# UV16_PDU.net
KiCad netlist of a schematic drawn in Altium Designer
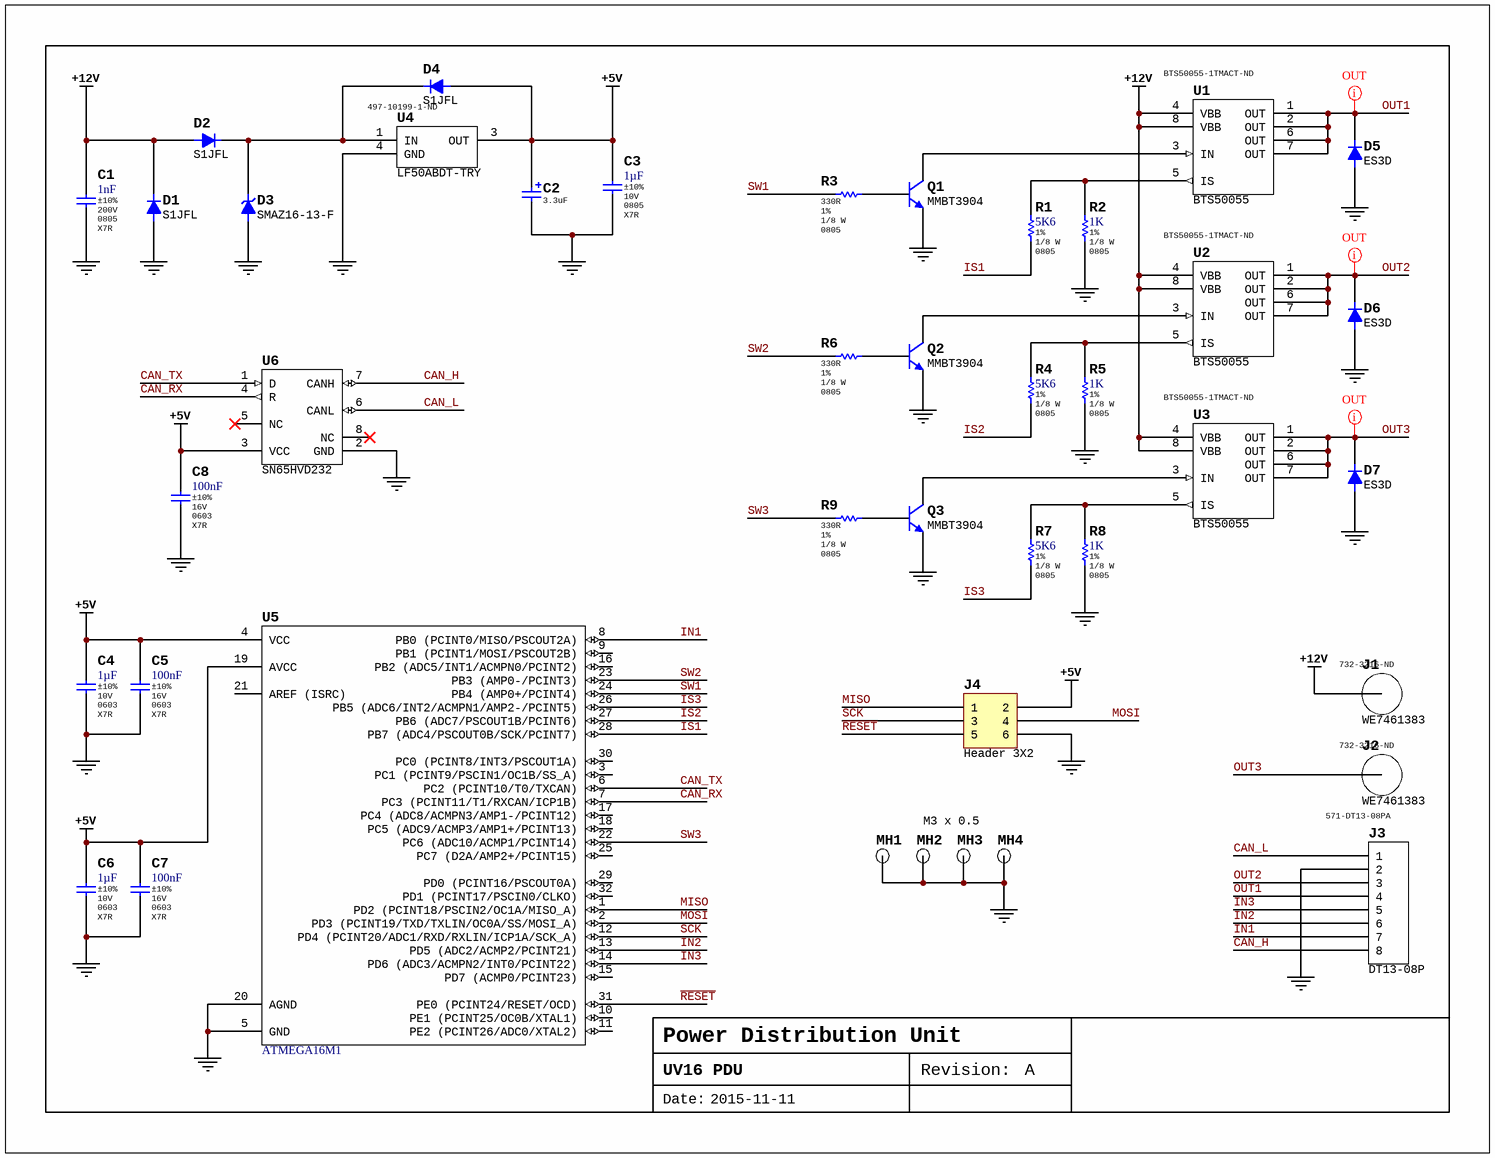
[diagram p0: UV16 PDU.SchDoc]

(export (version "E")
  (design (tool "Eeschema 10.0.6"))
  (components
    (comp (ref "C1")
      (value "1nF")
      (footprint "CAP-0805-M")
      (fields
        (field (name "PART NUMBER") "CC0805KRX7RABB102")
        (field (name "TOLERANCE") "±10%")
        (field (name "VOLTAGE") "200V")
        (field (name "PACKAGE") "0805")
        (field (name "TEMPERATURE COEFFICIENT") "X7R")
        (field (name "MANUFACTURER") "Yageo")
      )
      (libsource (lib "Capacitors") (part "Capacitor"))
    )
    (comp (ref "C2")
      (value "3.3uF")
      (footprint "CAPMP6032X21M")
      (fields (field (name "Comment") "TPSC335K035R0700"))
      (libsource (lib "UV16 PDU") (part "TPSC335K035R0700"))
    )
    (comp (ref "C3")
      (value "1µF")
      (footprint "CAP-0805-M")
      (fields
        (field (name "PART NUMBER") "CC0805KKX7R6BB105")
        (field (name "TOLERANCE") "±10%")
        (field (name "VOLTAGE") "10V")
        (field (name "PACKAGE") "0805")
        (field (name "TEMPERATURE COEFFICIENT") "X7R")
        (field (name "MANUFACTURER") "Yageo")
      )
      (libsource (lib "Capacitors") (part "Capacitor"))
    )
    (comp (ref "C4")
      (value "1µF")
      (footprint "CAP-0603-M")
      (fields
        (field (name "PART NUMBER") "CC0603KRX7R6BB105")
        (field (name "TOLERANCE") "±10%")
        (field (name "VOLTAGE") "10V")
        (field (name "PACKAGE") "0603")
        (field (name "TEMPERATURE COEFFICIENT") "X7R")
        (field (name "MANUFACTURER") "Yageo")
      )
      (libsource (lib "Capacitors") (part "Capacitor"))
    )
    (comp (ref "C5")
      (value "100nF")
      (footprint "CAP-0603-M")
      (fields
        (field (name "PART NUMBER") "CC0603KPX7R7BB104")
        (field (name "TOLERANCE") "±10%")
        (field (name "VOLTAGE") "16V")
        (field (name "PACKAGE") "0603")
        (field (name "TEMPERATURE COEFFICIENT") "X7R")
        (field (name "MANUFACTURER") "Yageo")
      )
      (libsource (lib "Capacitors") (part "Capacitor"))
    )
    (comp (ref "C6")
      (value "1µF")
      (footprint "CAP-0603-M")
      (fields
        (field (name "PART NUMBER") "CC0603KRX7R6BB105")
        (field (name "TOLERANCE") "±10%")
        (field (name "VOLTAGE") "10V")
        (field (name "PACKAGE") "0603")
        (field (name "TEMPERATURE COEFFICIENT") "X7R")
        (field (name "MANUFACTURER") "Yageo")
      )
      (libsource (lib "Capacitors") (part "Capacitor"))
    )
    (comp (ref "C7")
      (value "100nF")
      (footprint "CAP-0603-M")
      (fields
        (field (name "PART NUMBER") "CC0603KPX7R7BB104")
        (field (name "TOLERANCE") "±10%")
        (field (name "VOLTAGE") "16V")
        (field (name "PACKAGE") "0603")
        (field (name "TEMPERATURE COEFFICIENT") "X7R")
        (field (name "MANUFACTURER") "Yageo")
      )
      (libsource (lib "Capacitors") (part "Capacitor"))
    )
    (comp (ref "C8")
      (value "100nF")
      (footprint "CAP-0603-M")
      (fields
        (field (name "PART NUMBER") "CC0603KPX7R7BB104")
        (field (name "TOLERANCE") "±10%")
        (field (name "VOLTAGE") "16V")
        (field (name "PACKAGE") "0603")
        (field (name "TEMPERATURE COEFFICIENT") "X7R")
        (field (name "MANUFACTURER") "Yageo")
      )
      (libsource (lib "Capacitors") (part "Capacitor"))
    )
    (comp (ref "D1") (value "S1JFL") (footprint "DIOM3617X11M") (libsource (lib "UV16 PDU") (part "S1JFL")))
    (comp (ref "D2") (value "S1JFL") (footprint "DIOM3617X11M") (libsource (lib "UV16 PDU") (part "S1JFL")))
    (comp (ref "D3")
      (value "SMAZ16-13-F")
      (footprint "DIOM4326X23M")
      (libsource (lib "UV16 PDU") (part "SMAZ16-13-F"))
    )
    (comp (ref "D4") (value "S1JFL") (footprint "DIOM3617X11M") (libsource (lib "UV16 PDU") (part "S1JFL")))
    (comp (ref "D5") (value "ES3D") (footprint "DIOM6959X26M") (libsource (lib "UV16 PDU") (part "ES3D")))
    (comp (ref "D6") (value "ES3D") (footprint "DIOM6959X26M") (libsource (lib "UV16 PDU") (part "ES3D")))
    (comp (ref "D7") (value "ES3D") (footprint "DIOM6959X26M") (libsource (lib "UV16 PDU") (part "ES3D")))
    (comp (ref "J1")
      (value "WE7461383")
      (footprint "WE7461383")
      (fields (field (name "SUPPLIER PART NUMBER 1") "732-3216-ND"))
      (libsource (lib "UV16 PDU") (part "WE7461383"))
    )
    (comp (ref "J2")
      (value "WE7461383")
      (footprint "WE7461383")
      (fields (field (name "SUPPLIER PART NUMBER 1") "732-3216-ND"))
      (libsource (lib "UV16 PDU") (part "WE7461383"))
    )
    (comp (ref "J3")
      (value "DT13-08P")
      (footprint "DT13-08P")
      (description "DT Series 8-Pin Right Angle PCB Mount Receptacle")
      (fields (field (name "SUPPLIER PART NUMBER 1") "571-DT13-08PA"))
      (libsource (lib "UV16 PDU") (part "DT13-08P"))
    )
    (comp (ref "J4")
      (value "Header 3X2")
      (footprint "HDR2X3")
      (description "Header, 3-Pin, Dual row")
      (fields (field (name "PUBLISHER") "Altium Limited"))
      (libsource (lib "Miscellaneous Connectors") (part "Header 3X2"))
    )
    (comp (ref "MH1")
      (value "M3 x 0.5")
      (footprint "MH-M3-0.5")
      (libsource (lib "UV16 PDU") (part "MH-M3-0.5"))
    )
    (comp (ref "MH2")
      (value "M3 x 0.5")
      (footprint "MH-M3-0.5")
      (libsource (lib "UV16 PDU") (part "MH-M3-0.5"))
    )
    (comp (ref "MH3")
      (value "M3 x 0.5")
      (footprint "MH-M3-0.5")
      (libsource (lib "UV16 PDU") (part "MH-M3-0.5"))
    )
    (comp (ref "MH4")
      (value "M3 x 0.5")
      (footprint "MH-M3-0.5")
      (libsource (lib "UV16 PDU") (part "MH-M3-0.5"))
    )
    (comp (ref "Q1") (value "MMBT3904") (footprint "SOT23-3") (libsource (lib "UV16 PDU") (part "MMBT3904")))
    (comp (ref "Q2") (value "MMBT3904") (footprint "SOT23-3") (libsource (lib "UV16 PDU") (part "MMBT3904")))
    (comp (ref "Q3") (value "MMBT3904") (footprint "SOT23-3") (libsource (lib "UV16 PDU") (part "MMBT3904")))
    (comp (ref "R1")
      (value "5K6")
      (footprint "RES-0805-M")
      (fields
        (field (name "PART NUMBER") "RC0805FR-075K6L")
        (field (name "TOLERANCE") "1%")
        (field (name "POWER") "1/8 W")
        (field (name "PACKAGE") "0805")
        (field (name "MANUFACTURER") "Yageo")
      )
      (libsource (lib "Resistors") (part "Resistor"))
    )
    (comp (ref "R2")
      (value "1K")
      (footprint "RES-0805-M")
      (fields
        (field (name "PART NUMBER") "RC0805FR-071KL")
        (field (name "TOLERANCE") "1%")
        (field (name "POWER") "1/8 W")
        (field (name "PACKAGE") "0805")
        (field (name "MANUFACTURER") "Yageo")
      )
      (libsource (lib "Resistors") (part "Resistor"))
    )
    (comp (ref "R3")
      (value "330R")
      (footprint "RES-0805-M")
      (fields
        (field (name "PART NUMBER") "RC0805FR-07330RL")
        (field (name "TOLERANCE") "1%")
        (field (name "POWER") "1/8 W")
        (field (name "PACKAGE") "0805")
        (field (name "MANUFACTURER") "Yageo")
      )
      (libsource (lib "Resistors") (part "Resistor"))
    )
    (comp (ref "R4")
      (value "5K6")
      (footprint "RES-0805-M")
      (fields
        (field (name "PART NUMBER") "RC0805FR-075K6L")
        (field (name "TOLERANCE") "1%")
        (field (name "POWER") "1/8 W")
        (field (name "PACKAGE") "0805")
        (field (name "MANUFACTURER") "Yageo")
      )
      (libsource (lib "Resistors") (part "Resistor"))
    )
    (comp (ref "R5")
      (value "1K")
      (footprint "RES-0805-M")
      (fields
        (field (name "PART NUMBER") "RC0805FR-071KL")
        (field (name "TOLERANCE") "1%")
        (field (name "POWER") "1/8 W")
        (field (name "PACKAGE") "0805")
        (field (name "MANUFACTURER") "Yageo")
      )
      (libsource (lib "Resistors") (part "Resistor"))
    )
    (comp (ref "R6")
      (value "330R")
      (footprint "RES-0805-M")
      (fields
        (field (name "PART NUMBER") "RC0805FR-07330RL")
        (field (name "TOLERANCE") "1%")
        (field (name "POWER") "1/8 W")
        (field (name "PACKAGE") "0805")
        (field (name "MANUFACTURER") "Yageo")
      )
      (libsource (lib "Resistors") (part "Resistor"))
    )
    (comp (ref "R7")
      (value "5K6")
      (footprint "RES-0805-M")
      (fields
        (field (name "PART NUMBER") "RC0805FR-075K6L")
        (field (name "TOLERANCE") "1%")
        (field (name "POWER") "1/8 W")
        (field (name "PACKAGE") "0805")
        (field (name "MANUFACTURER") "Yageo")
      )
      (libsource (lib "Resistors") (part "Resistor"))
    )
    (comp (ref "R8")
      (value "1K")
      (footprint "RES-0805-M")
      (fields
        (field (name "PART NUMBER") "RC0805FR-071KL")
        (field (name "TOLERANCE") "1%")
        (field (name "POWER") "1/8 W")
        (field (name "PACKAGE") "0805")
        (field (name "MANUFACTURER") "Yageo")
      )
      (libsource (lib "Resistors") (part "Resistor"))
    )
    (comp (ref "R9")
      (value "330R")
      (footprint "RES-0805-M")
      (fields
        (field (name "PART NUMBER") "RC0805FR-07330RL")
        (field (name "TOLERANCE") "1%")
        (field (name "POWER") "1/8 W")
        (field (name "PACKAGE") "0805")
        (field (name "MANUFACTURER") "Yageo")
      )
      (libsource (lib "Resistors") (part "Resistor"))
    )
    (comp (ref "U1")
      (value "BTS50055")
      (footprint "P/PG-TO220-7-4")
      (fields (field (name "SUPPLIER PART NUMBER 1") "BTS50055-1TMACT-ND"))
      (libsource (lib "UV16 PDU") (part "BTS50055"))
    )
    (comp (ref "U2")
      (value "BTS50055")
      (footprint "P/PG-TO220-7-4")
      (fields (field (name "SUPPLIER PART NUMBER 1") "BTS50055-1TMACT-ND"))
      (libsource (lib "UV16 PDU") (part "BTS50055"))
    )
    (comp (ref "U3")
      (value "BTS50055")
      (footprint "P/PG-TO220-7-4")
      (fields (field (name "SUPPLIER PART NUMBER 1") "BTS50055-1TMACT-ND"))
      (libsource (lib "UV16 PDU") (part "BTS50055"))
    )
    (comp (ref "U4")
      (value "LF50ABDT-TRY")
      (footprint "TO-252-3")
      (fields (field (name "SUPPLIER PART NUMBER 1") "497-10199-1-ND"))
      (libsource (lib "UV16 PDU") (part "LF50ABDT-TRY"))
    )
    (comp (ref "U5")
      (value "ATMEGA16M1")
      (footprint "32-TQFP-7x7-0.8")
      (libsource (lib "UV16 PDU") (part "ATMEGA16M1-15AZ"))
    )
    (comp (ref "U6")
      (value "SN65HVD232")
      (footprint "8-SOIC")
      (description "CAN transceiver")
      (libsource (lib "UV16 PDU") (part "SN65HVD232"))
    )
  )
  (nets
    (net (code "1") (name "+5V") (class "Default")
      (node (ref "C2") (pin "1") (pinfunction "1_1") (pintype "passive"))
      (node (ref "C3") (pin "2") (pinfunction "2_2") (pintype "passive"))
      (node (ref "C4") (pin "2") (pinfunction "2_2") (pintype "passive"))
      (node (ref "C5") (pin "2") (pinfunction "2_2") (pintype "passive"))
      (node (ref "C6") (pin "1") (pinfunction "1_1") (pintype "passive"))
      (node (ref "C7") (pin "1") (pinfunction "1_1") (pintype "passive"))
      (node (ref "C8") (pin "1") (pinfunction "1_1") (pintype "passive"))
      (node (ref "D4") (pin "2") (pinfunction "A_2") (pintype "passive"))
      (node (ref "J4") (pin "2") (pinfunction "2_2") (pintype "passive"))
      (node (ref "U4") (pin "3") (pinfunction "OUT_3") (pintype "power_in"))
      (node (ref "U5") (pin "19") (pinfunction "AVCC_19") (pintype "power_in"))
      (node (ref "U5") (pin "4") (pinfunction "VCC_4") (pintype "power_in"))
      (node (ref "U6") (pin "3") (pinfunction "VCC_3") (pintype "power_in"))
    )
    (net (code "2") (name "+12V") (class "Default")
      (node (ref "C1") (pin "2") (pinfunction "2_2") (pintype "passive"))
      (node (ref "D1") (pin "1") (pinfunction "K_1") (pintype "passive"))
      (node (ref "D2") (pin "2") (pinfunction "A_2") (pintype "passive"))
      (node (ref "J1") (pin "0") (pinfunction "0_0") (pintype "passive"))
      (node (ref "U1") (pin "4") (pinfunction "VBB_4") (pintype "power_in"))
      (node (ref "U1") (pin "8") (pinfunction "VBB_8") (pintype "passive"))
      (node (ref "U2") (pin "4") (pinfunction "VBB_4") (pintype "power_in"))
      (node (ref "U2") (pin "8") (pinfunction "VBB_8") (pintype "passive"))
      (node (ref "U3") (pin "4") (pinfunction "VBB_4") (pintype "power_in"))
      (node (ref "U3") (pin "8") (pinfunction "VBB_8") (pintype "passive"))
    )
    (net (code "3") (name "/CAN_H") (class "Default")
      (node (ref "J3") (pin "8") (pinfunction "8_8") (pintype "passive"))
      (node (ref "U6") (pin "7") (pinfunction "CANH_7") (pintype "bidirectional"))
    )
    (net (code "4") (name "/CAN_L") (class "Default")
      (node (ref "J3") (pin "1") (pinfunction "1_1") (pintype "passive"))
      (node (ref "U6") (pin "6") (pinfunction "CANL_6") (pintype "bidirectional"))
    )
    (net (code "5") (name "/CAN_RX") (class "Default")
      (node (ref "U5") (pin "7") (pinfunction "PC3_(PCINT11/T1/RXCAN/ICP1B)_7") (pintype "bidirectional"))
      (node (ref "U6") (pin "4") (pinfunction "R_4") (pintype "output"))
    )
    (net (code "6") (name "/CAN_TX") (class "Default")
      (node (ref "U5") (pin "6") (pinfunction "PC2_(PCINT10/T0/TXCAN)_6") (pintype "bidirectional"))
      (node (ref "U6") (pin "1") (pinfunction "D_1") (pintype "input"))
    )
    (net (code "7") (name "/IN1") (class "Default")
      (node (ref "J3") (pin "7") (pinfunction "7_7") (pintype "passive"))
      (node (ref "U5") (pin "8") (pinfunction "PB0_(PCINT0/MISO/PSCOUT2A)_8") (pintype "bidirectional"))
    )
    (net (code "8") (name "/IN2") (class "Default")
      (node (ref "J3") (pin "6") (pinfunction "6_6") (pintype "passive"))
      (node (ref "U5") (pin "13") (pinfunction "PD5_(ADC2/ACMP2/PCINT21)_13") (pintype "bidirectional"))
    )
    (net (code "9") (name "/IN3") (class "Default")
      (node (ref "J3") (pin "5") (pinfunction "5_5") (pintype "passive"))
      (node (ref "U5") (pin "14") (pinfunction "PD6_(ADC3/ACMPN2/INT0/PCINT22)_14") (pintype "bidirectional"))
    )
    (net (code "10") (name "/IS1") (class "Default")
      (node (ref "R1") (pin "1") (pinfunction "1_1") (pintype "passive"))
      (node (ref "U5") (pin "28") (pinfunction "PB7_(ADC4/PSCOUT0B/SCK/PCINT7)_28") (pintype "bidirectional"))
    )
    (net (code "11") (name "/IS2") (class "Default")
      (node (ref "R4") (pin "1") (pinfunction "1_1") (pintype "passive"))
      (node (ref "U5") (pin "27") (pinfunction "PB6_(ADC7/PSCOUT1B/PCINT6)_27") (pintype "bidirectional"))
    )
    (net (code "12") (name "/IS3") (class "Default")
      (node (ref "R7") (pin "1") (pinfunction "1_1") (pintype "passive"))
      (node (ref "U5") (pin "26") (pinfunction "PB5_(ADC6/INT2/ACMPN1/AMP2-/PCINT5)_26") (pintype "bidirectional"))
    )
    (net (code "13") (name "/MISO") (class "Default")
      (node (ref "J4") (pin "1") (pinfunction "1_1") (pintype "passive"))
      (node (ref "U5") (pin "1") (pinfunction "PD2_(PCINT18/PSCIN2/OC1A/MISO_A)_1") (pintype "bidirectional"))
    )
    (net (code "14") (name "/MOSI") (class "Default")
      (node (ref "J4") (pin "4") (pinfunction "4_4") (pintype "passive"))
      (node (ref "U5") (pin "2") (pinfunction "PD3_(PCINT19/TXD/TXLIN/OC0A/SS/MOSI_A)_2") (pintype "bidirectional"))
    )
    (net (code "15") (name "/OUT1") (class "Default")
      (node (ref "D5") (pin "1") (pinfunction "K_1") (pintype "passive"))
      (node (ref "J3") (pin "4") (pinfunction "4_4") (pintype "passive"))
      (node (ref "U1") (pin "1") (pinfunction "OUT_1") (pintype "power_in"))
      (node (ref "U1") (pin "2") (pinfunction "OUT_2") (pintype "power_in"))
      (node (ref "U1") (pin "6") (pinfunction "OUT_6") (pintype "power_in"))
      (node (ref "U1") (pin "7") (pinfunction "OUT_7") (pintype "power_in"))
    )
    (net (code "16") (name "/OUT2") (class "Default")
      (node (ref "D6") (pin "1") (pinfunction "K_1") (pintype "passive"))
      (node (ref "J3") (pin "3") (pinfunction "3_3") (pintype "passive"))
      (node (ref "U2") (pin "1") (pinfunction "OUT_1") (pintype "power_in"))
      (node (ref "U2") (pin "2") (pinfunction "OUT_2") (pintype "power_in"))
      (node (ref "U2") (pin "6") (pinfunction "OUT_6") (pintype "power_in"))
      (node (ref "U2") (pin "7") (pinfunction "OUT_7") (pintype "power_in"))
    )
    (net (code "17") (name "/OUT3") (class "Default")
      (node (ref "D7") (pin "1") (pinfunction "K_1") (pintype "passive"))
      (node (ref "J2") (pin "0") (pinfunction "0_0") (pintype "passive"))
      (node (ref "U3") (pin "1") (pinfunction "OUT_1") (pintype "power_in"))
      (node (ref "U3") (pin "2") (pinfunction "OUT_2") (pintype "power_in"))
      (node (ref "U3") (pin "6") (pinfunction "OUT_6") (pintype "power_in"))
      (node (ref "U3") (pin "7") (pinfunction "OUT_7") (pintype "power_in"))
    )
    (net (code "18") (name "/SCK") (class "Default")
      (node (ref "J4") (pin "3") (pinfunction "3_3") (pintype "passive"))
      (node (ref "U5") (pin "12") (pinfunction "PD4_(PCINT20/ADC1/RXD/RXLIN/ICP1A/SCK_A)_12") (pintype "bidirectional"))
    )
    (net (code "19") (name "/SW1") (class "Default")
      (node (ref "R3") (pin "1") (pinfunction "1_1") (pintype "passive"))
      (node (ref "U5") (pin "24") (pinfunction "PB4_(AMP0+/PCINT4)_24") (pintype "bidirectional"))
    )
    (net (code "20") (name "/SW2") (class "Default")
      (node (ref "R6") (pin "1") (pinfunction "1_1") (pintype "passive"))
      (node (ref "U5") (pin "23") (pinfunction "PB3_(AMP0-/PCINT3)_23") (pintype "bidirectional"))
    )
    (net (code "21") (name "/SW3") (class "Default")
      (node (ref "R9") (pin "1") (pinfunction "1_1") (pintype "passive"))
      (node (ref "U5") (pin "22") (pinfunction "PC6_(ADC10/ACMP1/PCINT14)_22") (pintype "bidirectional"))
    )
    (net (code "22") (name "/~{RESET}") (class "Default")
      (node (ref "J4") (pin "5") (pinfunction "5_5") (pintype "passive"))
      (node (ref "U5") (pin "31") (pinfunction "PE0_(PCINT24/RESET/OCD)_31") (pintype "bidirectional"))
    )
    (net (code "23") (name "GND") (class "Default")
      (node (ref "C1") (pin "1") (pinfunction "1_1") (pintype "passive"))
      (node (ref "C2") (pin "2") (pinfunction "2_2") (pintype "passive"))
      (node (ref "C3") (pin "1") (pinfunction "1_1") (pintype "passive"))
      (node (ref "C4") (pin "1") (pinfunction "1_1") (pintype "passive"))
      (node (ref "C5") (pin "1") (pinfunction "1_1") (pintype "passive"))
      (node (ref "C6") (pin "2") (pinfunction "2_2") (pintype "passive"))
      (node (ref "C7") (pin "2") (pinfunction "2_2") (pintype "passive"))
      (node (ref "C8") (pin "2") (pinfunction "2_2") (pintype "passive"))
      (node (ref "D1") (pin "2") (pinfunction "A_2") (pintype "passive"))
      (node (ref "D3") (pin "2") (pinfunction "A_2") (pintype "passive"))
      (node (ref "D5") (pin "2") (pinfunction "A_2") (pintype "passive"))
      (node (ref "D6") (pin "2") (pinfunction "A_2") (pintype "passive"))
      (node (ref "D7") (pin "2") (pinfunction "A_2") (pintype "passive"))
      (node (ref "J3") (pin "2") (pinfunction "2_2") (pintype "passive"))
      (node (ref "J4") (pin "6") (pinfunction "6_6") (pintype "passive"))
      (node (ref "MH1") (pin "0") (pinfunction "0_0") (pintype "passive"))
      (node (ref "MH2") (pin "0") (pinfunction "0_0") (pintype "passive"))
      (node (ref "MH3") (pin "0") (pinfunction "0_0") (pintype "passive"))
      (node (ref "MH4") (pin "0") (pinfunction "0_0") (pintype "passive"))
      (node (ref "Q1") (pin "2") (pinfunction "E_2") (pintype "passive"))
      (node (ref "Q2") (pin "2") (pinfunction "E_2") (pintype "passive"))
      (node (ref "Q3") (pin "2") (pinfunction "E_2") (pintype "passive"))
      (node (ref "R2") (pin "2") (pinfunction "2_2") (pintype "passive"))
      (node (ref "R5") (pin "2") (pinfunction "2_2") (pintype "passive"))
      (node (ref "R8") (pin "2") (pinfunction "2_2") (pintype "passive"))
      (node (ref "U4") (pin "4") (pinfunction "GND_4") (pintype "passive"))
      (node (ref "U5") (pin "20") (pinfunction "AGND_20") (pintype "power_in"))
      (node (ref "U5") (pin "5") (pinfunction "GND_5") (pintype "power_in"))
      (node (ref "U6") (pin "2") (pinfunction "GND_2") (pintype "power_in"))
    )
    (net (code "24") (name "Net-(D2-K)") (class "Default")
      (node (ref "D2") (pin "1") (pinfunction "K_1") (pintype "passive"))
      (node (ref "D3") (pin "1") (pinfunction "K_1") (pintype "passive"))
      (node (ref "D4") (pin "1") (pinfunction "K_1") (pintype "passive"))
      (node (ref "U4") (pin "1") (pinfunction "IN_1") (pintype "power_in"))
    )
    (net (code "25") (name "Net-(Q1-B)") (class "Default")
      (node (ref "Q1") (pin "1") (pinfunction "B_1") (pintype "passive"))
      (node (ref "R3") (pin "2") (pinfunction "2_2") (pintype "passive"))
    )
    (net (code "26") (name "Net-(Q1-C)") (class "Default")
      (node (ref "Q1") (pin "3") (pinfunction "C_3") (pintype "passive"))
      (node (ref "U1") (pin "3") (pinfunction "IN_3") (pintype "input"))
    )
    (net (code "27") (name "Net-(Q2-B)") (class "Default")
      (node (ref "Q2") (pin "1") (pinfunction "B_1") (pintype "passive"))
      (node (ref "R6") (pin "2") (pinfunction "2_2") (pintype "passive"))
    )
    (net (code "28") (name "Net-(Q2-C)") (class "Default")
      (node (ref "Q2") (pin "3") (pinfunction "C_3") (pintype "passive"))
      (node (ref "U2") (pin "3") (pinfunction "IN_3") (pintype "input"))
    )
    (net (code "29") (name "Net-(Q3-B)") (class "Default")
      (node (ref "Q3") (pin "1") (pinfunction "B_1") (pintype "passive"))
      (node (ref "R9") (pin "2") (pinfunction "2_2") (pintype "passive"))
    )
    (net (code "30") (name "Net-(Q3-C)") (class "Default")
      (node (ref "Q3") (pin "3") (pinfunction "C_3") (pintype "passive"))
      (node (ref "U3") (pin "3") (pinfunction "IN_3") (pintype "input"))
    )
    (net (code "31") (name "Net-(U1-IS)") (class "Default")
      (node (ref "R1") (pin "2") (pinfunction "2_2") (pintype "passive"))
      (node (ref "R2") (pin "1") (pinfunction "1_1") (pintype "passive"))
      (node (ref "U1") (pin "5") (pinfunction "IS_5") (pintype "output"))
    )
    (net (code "32") (name "Net-(U2-IS)") (class "Default")
      (node (ref "R4") (pin "2") (pinfunction "2_2") (pintype "passive"))
      (node (ref "R5") (pin "1") (pinfunction "1_1") (pintype "passive"))
      (node (ref "U2") (pin "5") (pinfunction "IS_5") (pintype "output"))
    )
    (net (code "33") (name "Net-(U3-IS)") (class "Default")
      (node (ref "R7") (pin "2") (pinfunction "2_2") (pintype "passive"))
      (node (ref "R8") (pin "1") (pinfunction "1_1") (pintype "passive"))
      (node (ref "U3") (pin "5") (pinfunction "IS_5") (pintype "output"))
    )
    (net (code "34") (name "unconnected-(U5-AREF_(ISRC)-Pad21)") (class "Default")
      (node (ref "U5") (pin "21") (pinfunction "AREF_(ISRC)_21") (pintype "power_in"))
    )
    (net (code "35") (name "unconnected-(U5-PB1_(PCINT1{slash}MOSI{slash}PSCOUT2B)-Pad9)") (class "Default")
      (node (ref "U5") (pin "9") (pinfunction "PB1_(PCINT1/MOSI/PSCOUT2B)_9") (pintype "bidirectional"))
    )
    (net (code "36") (name "unconnected-(U5-PB2_(ADC5{slash}INT1{slash}ACMPN0{slash}PCINT2)-Pad16)") (class "Default")
      (node (ref "U5") (pin "16") (pinfunction "PB2_(ADC5/INT1/ACMPN0/PCINT2)_16") (pintype "bidirectional"))
    )
    (net (code "37") (name "unconnected-(U5-PC0_(PCINT8{slash}INT3{slash}PSCOUT1A)-Pad30)") (class "Default")
      (node (ref "U5") (pin "30") (pinfunction "PC0_(PCINT8/INT3/PSCOUT1A)_30") (pintype "bidirectional"))
    )
    (net (code "38") (name "unconnected-(U5-PC1_(PCINT9{slash}PSCIN1{slash}OC1B{slash}SS_A)-Pad3)") (class "Default")
      (node (ref "U5") (pin "3") (pinfunction "PC1_(PCINT9/PSCIN1/OC1B/SS_A)_3") (pintype "bidirectional"))
    )
    (net (code "39") (name "unconnected-(U5-PC4_(ADC8{slash}ACMPN3{slash}AMP1-{slash}PCINT12)-Pad17)") (class "Default")
      (node (ref "U5") (pin "17") (pinfunction "PC4_(ADC8/ACMPN3/AMP1-/PCINT12)_17") (pintype "bidirectional"))
    )
    (net (code "40") (name "unconnected-(U5-PC5_(ADC9{slash}ACMP3{slash}AMP1+{slash}PCINT13)-Pad18)") (class "Default")
      (node (ref "U5") (pin "18") (pinfunction "PC5_(ADC9/ACMP3/AMP1+/PCINT13)_18") (pintype "bidirectional"))
    )
    (net (code "41") (name "unconnected-(U5-PC7_(D2A{slash}AMP2+{slash}PCINT15)-Pad25)") (class "Default")
      (node (ref "U5") (pin "25") (pinfunction "PC7_(D2A/AMP2+/PCINT15)_25") (pintype "bidirectional"))
    )
    (net (code "42") (name "unconnected-(U5-PD0_(PCINT16{slash}PSCOUT0A)-Pad29)") (class "Default")
      (node (ref "U5") (pin "29") (pinfunction "PD0_(PCINT16/PSCOUT0A)_29") (pintype "bidirectional"))
    )
    (net (code "43") (name "unconnected-(U5-PD1_(PCINT17{slash}PSCIN0{slash}CLKO)-Pad32)") (class "Default")
      (node (ref "U5") (pin "32") (pinfunction "PD1_(PCINT17/PSCIN0/CLKO)_32") (pintype "bidirectional"))
    )
    (net (code "44") (name "unconnected-(U5-PD7_(ACMP0{slash}PCINT23)-Pad15)") (class "Default")
      (node (ref "U5") (pin "15") (pinfunction "PD7_(ACMP0/PCINT23)_15") (pintype "bidirectional"))
    )
    (net (code "45") (name "unconnected-(U5-PE1_(PCINT25{slash}OC0B{slash}XTAL1)-Pad10)") (class "Default")
      (node (ref "U5") (pin "10") (pinfunction "PE1_(PCINT25/OC0B/XTAL1)_10") (pintype "bidirectional"))
    )
    (net (code "46") (name "unconnected-(U5-PE2_(PCINT26{slash}ADC0{slash}XTAL2)-Pad11)") (class "Default")
      (node (ref "U5") (pin "11") (pinfunction "PE2_(PCINT26/ADC0/XTAL2)_11") (pintype "bidirectional"))
    )
    (net (code "47") (name "unconnected-(U6-NC-Pad5)") (class "Default")
      (node (ref "U6") (pin "5") (pinfunction "NC_5") (pintype "passive+no_connect"))
    )
    (net (code "48") (name "unconnected-(U6-NC-Pad8)") (class "Default")
      (node (ref "U6") (pin "8") (pinfunction "NC_8") (pintype "passive+no_connect"))
    )
  )
)
